# powerboard.net
KiCad netlist of a schematic drawn in EAGLE
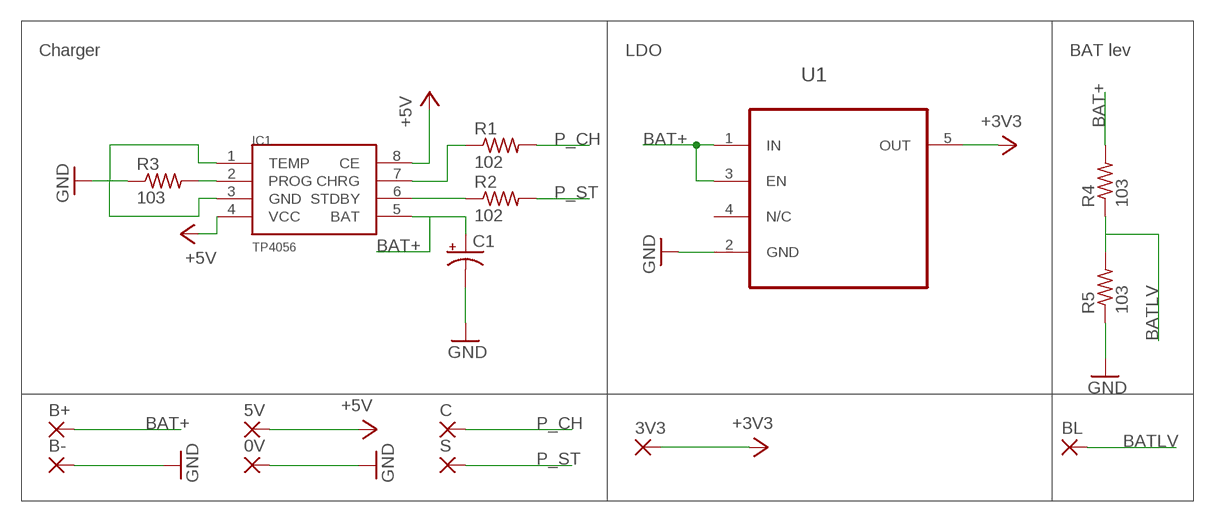
[diagram p0: schematic, sheet 1]

(export (version "E")
  (design (tool "Eeschema 10.0.6"))
  (components
    (comp (ref "0V")
      (value "SMD5")
      (footprint "eagle-import:SMD2,54-5,08")
      (libsource (lib "eagle-import") (part "SMD5"))
    )
    (comp (ref "3V3")
      (value "SMD5")
      (footprint "eagle-import:SMD2,54-5,08")
      (libsource (lib "eagle-import") (part "SMD5"))
    )
    (comp (ref "5V")
      (value "SMD5")
      (footprint "eagle-import:SMD2,54-5,08")
      (libsource (lib "eagle-import") (part "SMD5"))
    )
    (comp (ref "B+")
      (value "SMD5")
      (footprint "eagle-import:SMD2,54-5,08")
      (libsource (lib "eagle-import") (part "SMD5"))
    )
    (comp (ref "B-")
      (value "SMD5")
      (footprint "eagle-import:SMD2,54-5,08")
      (libsource (lib "eagle-import") (part "SMD5"))
    )
    (comp (ref "BL")
      (value "SMD5")
      (footprint "eagle-import:SMD2,54-5,08")
      (libsource (lib "eagle-import") (part "SMD5"))
    )
    (comp (ref "C")
      (value "SMD5")
      (footprint "eagle-import:SMD2,54-5,08")
      (libsource (lib "eagle-import") (part "SMD5"))
    )
    (comp (ref "C1")
      (value "CPOL-USR/2012-12R")
      (footprint "eagle-import:R_2012-12R")
      (libsource (lib "eagle-import") (part "CPOL-USR/2012-12R"))
    )
    (comp (ref "IC1")
      (value "TP4056")
      (footprint "eagle-import:SOP-8")
      (libsource (lib "eagle-import") (part "TP4056"))
    )
    (comp (ref "R1")
      (value "102")
      (footprint "eagle-import:M2012")
      (libsource (lib "eagle-import") (part "R-US_M2012"))
    )
    (comp (ref "R2")
      (value "102")
      (footprint "eagle-import:M2012")
      (libsource (lib "eagle-import") (part "R-US_M2012"))
    )
    (comp (ref "R3")
      (value "103")
      (footprint "eagle-import:M2012")
      (libsource (lib "eagle-import") (part "R-US_M2012"))
    )
    (comp (ref "R4")
      (value "103")
      (footprint "eagle-import:M2012")
      (libsource (lib "eagle-import") (part "R-US_M2012"))
    )
    (comp (ref "R5")
      (value "103")
      (footprint "eagle-import:M2012")
      (libsource (lib "eagle-import") (part "R-US_M2012"))
    )
    (comp (ref "S")
      (value "SMD5")
      (footprint "eagle-import:SMD2,54-5,08")
      (libsource (lib "eagle-import") (part "SMD5"))
    )
    (comp (ref "U1")
      (value "TLV70033DDCT")
      (footprint "eagle-import:SOT95P280X110-5N")
      (libsource (lib "eagle-import") (part "TLV70033DDCT"))
    )
  )
  (nets
    (net (code "1") (name "+3V3") (class "Default")
      (node (ref "3V3") (pin "1") (pinfunction "P_1") (pintype "passive"))
      (node (ref "U1") (pin "5") (pinfunction "OUT_5") (pintype "output"))
    )
    (net (code "2") (name "+5V") (class "Default")
      (node (ref "5V") (pin "1") (pinfunction "P_1") (pintype "passive"))
      (node (ref "IC1") (pin "4") (pinfunction "VCC_4") (pintype "bidirectional"))
      (node (ref "IC1") (pin "8") (pinfunction "CE_8") (pintype "bidirectional"))
    )
    (net (code "3") (name "/BAT+") (class "Default")
      (node (ref "B+") (pin "1") (pinfunction "P_1") (pintype "passive"))
      (node (ref "C1") (pin "+") (pinfunction "+_+") (pintype "passive"))
      (node (ref "IC1") (pin "5") (pinfunction "BAT_5") (pintype "bidirectional"))
      (node (ref "R4") (pin "2") (pinfunction "2_2") (pintype "passive"))
      (node (ref "U1") (pin "1") (pinfunction "IN_1") (pintype "input"))
      (node (ref "U1") (pin "3") (pinfunction "EN_3") (pintype "input"))
    )
    (net (code "4") (name "/BATLV") (class "Default")
      (node (ref "BL") (pin "1") (pinfunction "P_1") (pintype "passive"))
      (node (ref "R4") (pin "1") (pinfunction "1_1") (pintype "passive"))
      (node (ref "R5") (pin "2") (pinfunction "2_2") (pintype "passive"))
    )
    (net (code "5") (name "/P_CH") (class "Default")
      (node (ref "C") (pin "1") (pinfunction "P_1") (pintype "passive"))
      (node (ref "R1") (pin "2") (pinfunction "2_2") (pintype "passive"))
    )
    (net (code "6") (name "/P_ST") (class "Default")
      (node (ref "R2") (pin "2") (pinfunction "2_2") (pintype "passive"))
      (node (ref "S") (pin "1") (pinfunction "P_1") (pintype "passive"))
    )
    (net (code "7") (name "GND") (class "Default")
      (node (ref "0V") (pin "1") (pinfunction "P_1") (pintype "passive"))
      (node (ref "B-") (pin "1") (pinfunction "P_1") (pintype "passive"))
      (node (ref "C1") (pin "-") (pinfunction "-_-") (pintype "passive"))
      (node (ref "IC1") (pin "1") (pinfunction "TEMP_1") (pintype "bidirectional"))
      (node (ref "IC1") (pin "3") (pinfunction "GND_3") (pintype "bidirectional"))
      (node (ref "R3") (pin "1") (pinfunction "1_1") (pintype "passive"))
      (node (ref "R5") (pin "1") (pinfunction "1_1") (pintype "passive"))
      (node (ref "U1") (pin "2") (pinfunction "GND_2") (pintype "passive"))
    )
    (net (code "8") (name "Net-(IC1-CHRG)") (class "Default")
      (node (ref "IC1") (pin "7") (pinfunction "CHRG_7") (pintype "bidirectional"))
      (node (ref "R1") (pin "1") (pinfunction "1_1") (pintype "passive"))
    )
    (net (code "9") (name "Net-(IC1-PROG)") (class "Default")
      (node (ref "IC1") (pin "2") (pinfunction "PROG_2") (pintype "bidirectional"))
      (node (ref "R3") (pin "2") (pinfunction "2_2") (pintype "passive"))
    )
    (net (code "10") (name "Net-(IC1-STDBY)") (class "Default")
      (node (ref "IC1") (pin "6") (pinfunction "STDBY_6") (pintype "bidirectional"))
      (node (ref "R2") (pin "1") (pinfunction "1_1") (pintype "passive"))
    )
    (net (code "11") (name "unconnected-(U1-N{slash}C-Pad4)") (class "Default")
      (node (ref "U1") (pin "4") (pinfunction "N/C_4") (pintype "no_connect"))
    )
  )
)
